# LD_driver.net
KiCad netlist of a schematic drawn in Altium Designer
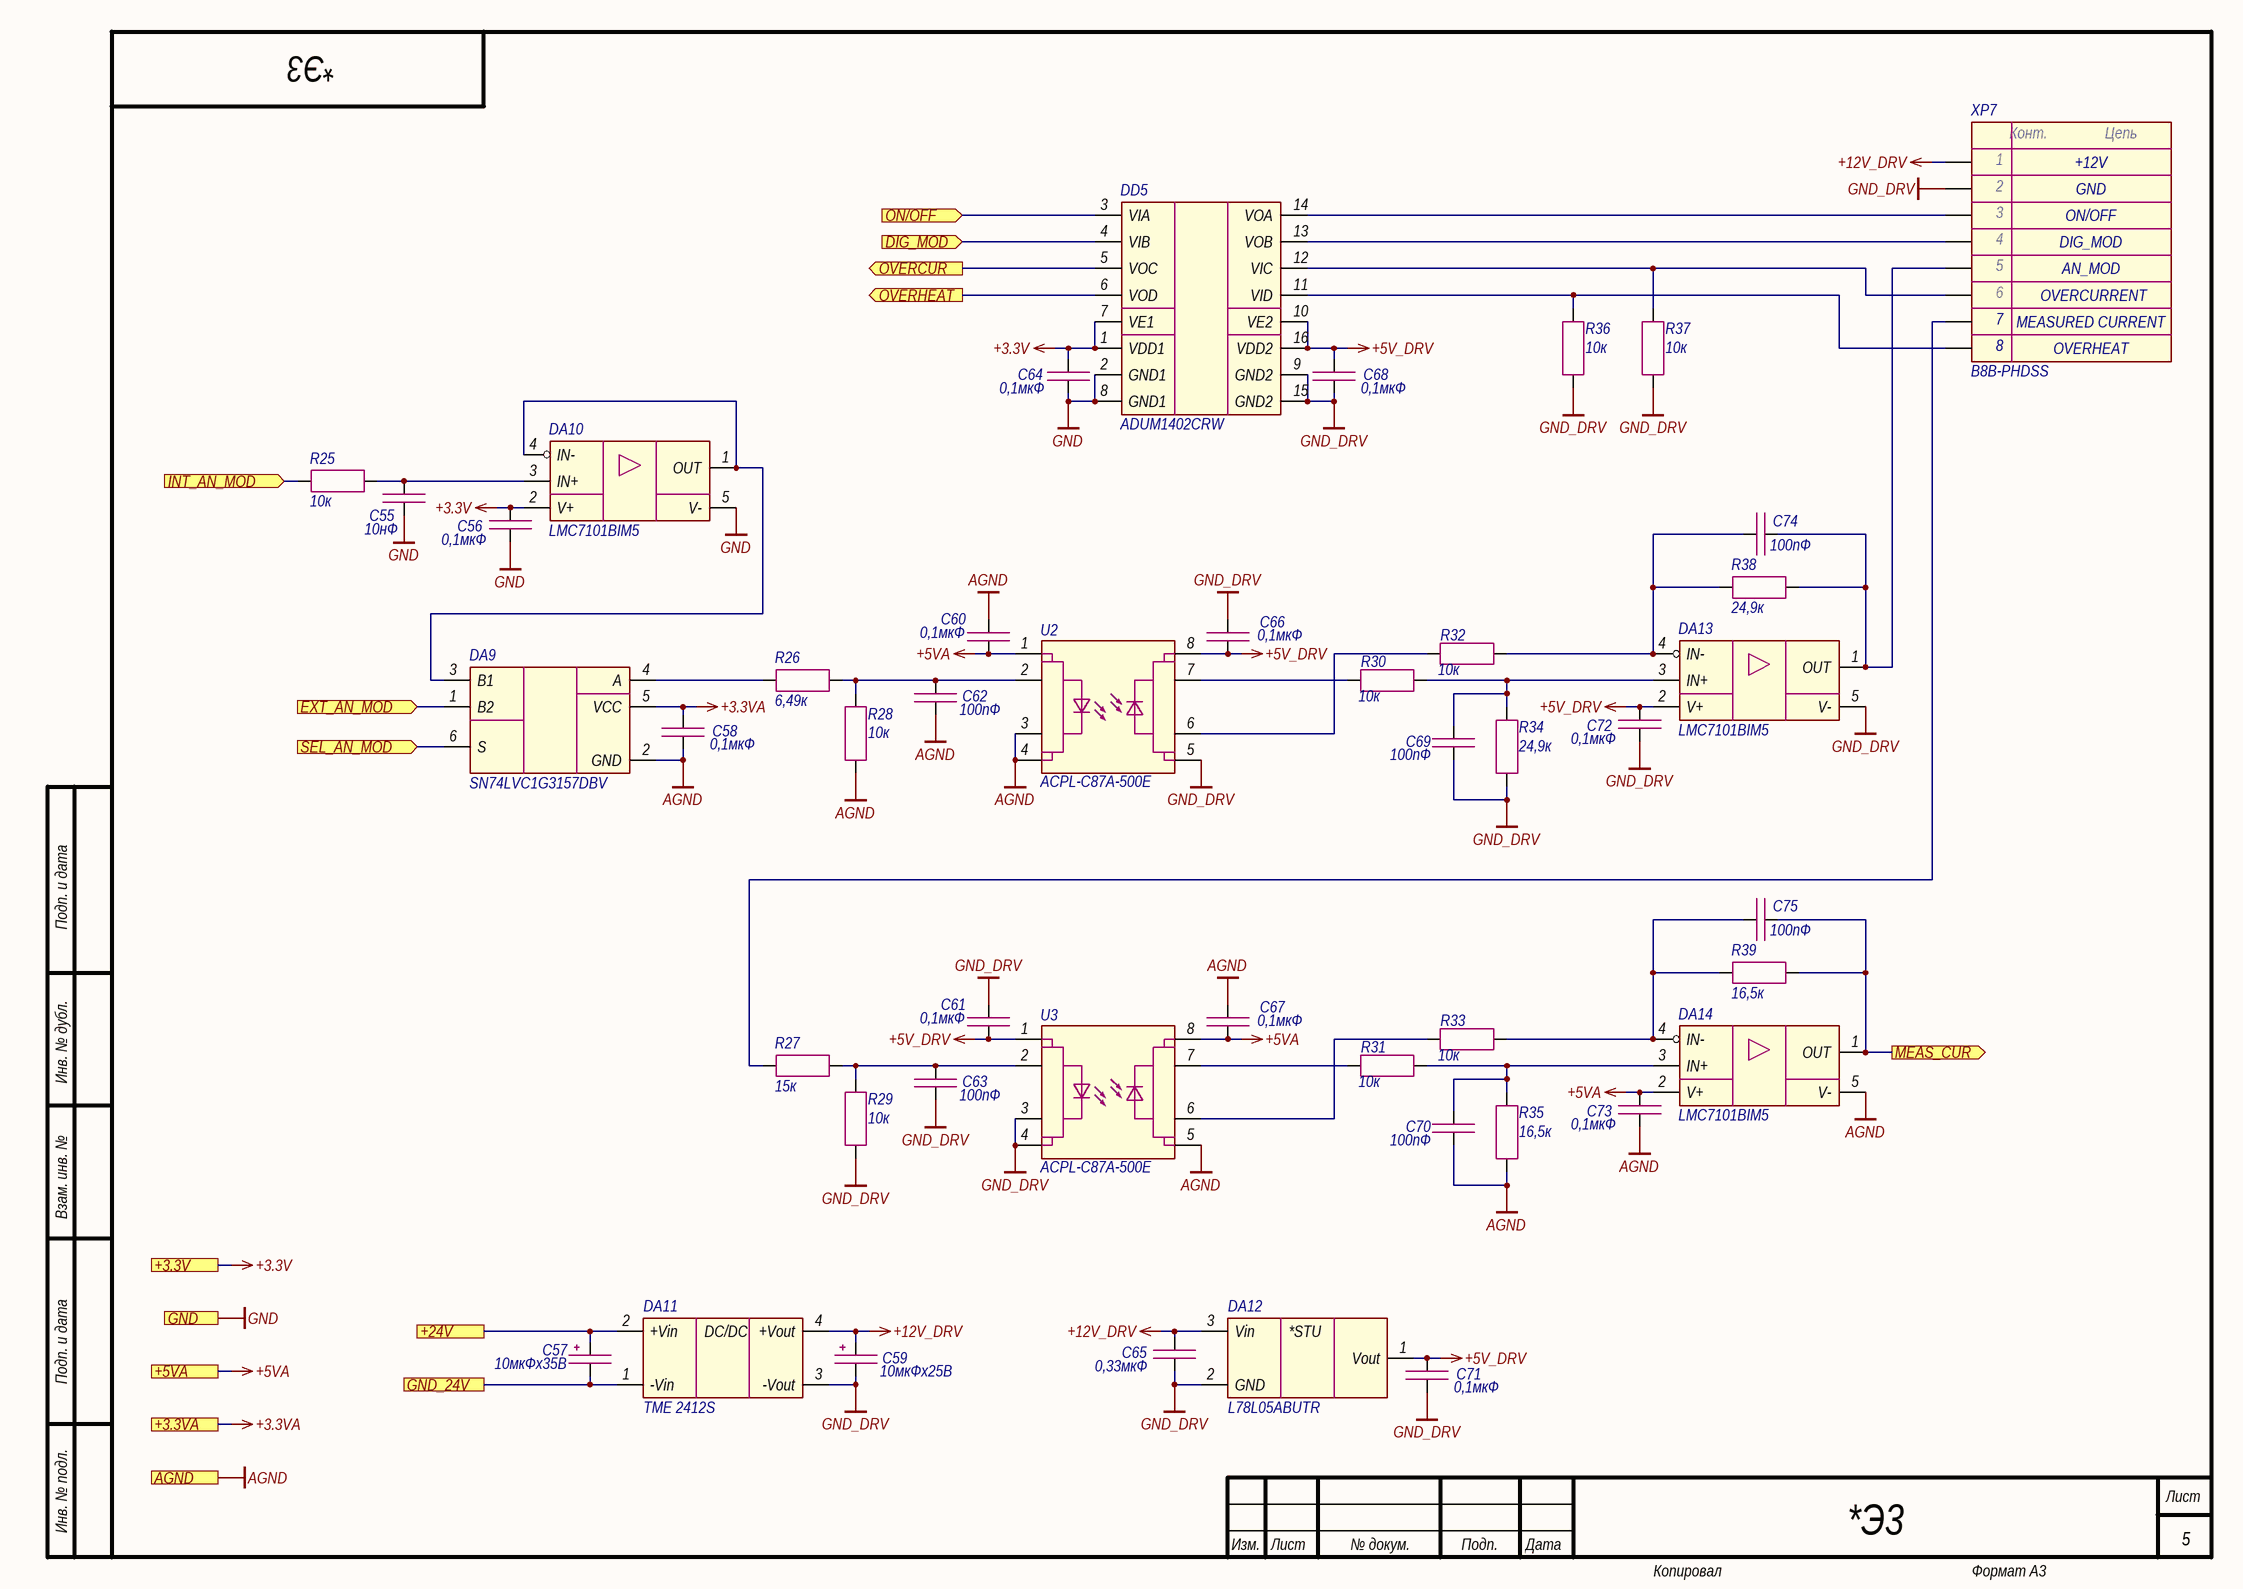
[diagram p0: LD_driver.SchDoc]

(export (version "E")
  (design (tool "Eeschema 10.0.6"))
  (components
    (comp (ref "C55")
      (value "10нФ")
      (footprint "Pcb_library:CAP_0603")
      (fields (field (name "MANUFACTURER") "Murata"))
      (libsource (lib "Schem_library") (part "Capacitor"))
    )
    (comp (ref "C56")
      (value "0,1мкФ")
      (footprint "Pcb_library:CAP_0603")
      (fields (field (name "MANUFACTURER") "Murata"))
      (libsource (lib "Schem_library") (part "Capacitor"))
    )
    (comp (ref "C57")
      (value "10мкФх35B")
      (footprint "Pcb_library:CAP_C")
      (libsource (lib "Schem_library") (part "Capacitor_Polar"))
    )
    (comp (ref "C58")
      (value "0,1мкФ")
      (footprint "Pcb_library:CAP_0603")
      (fields (field (name "MANUFACTURER") "Murata"))
      (libsource (lib "Schem_library") (part "Capacitor"))
    )
    (comp (ref "C59")
      (value "10мкФх25B")
      (footprint "Pcb_library:CAP_C")
      (libsource (lib "Schem_library") (part "Capacitor_Polar"))
    )
    (comp (ref "C60")
      (value "0,1мкФ")
      (footprint "Pcb_library:CAP_0603")
      (fields (field (name "MANUFACTURER") "Murata"))
      (libsource (lib "Schem_library") (part "Capacitor"))
    )
    (comp (ref "C61")
      (value "0,1мкФ")
      (footprint "Pcb_library:CAP_0603")
      (fields (field (name "MANUFACTURER") "Murata"))
      (libsource (lib "Schem_library") (part "Capacitor"))
    )
    (comp (ref "C62")
      (value "100пФ")
      (footprint "Pcb_library:CAP_0603")
      (fields (field (name "MANUFACTURER") "Murata"))
      (libsource (lib "Schem_library") (part "Capacitor"))
    )
    (comp (ref "C63")
      (value "100пФ")
      (footprint "Pcb_library:CAP_0603")
      (fields (field (name "MANUFACTURER") "Murata"))
      (libsource (lib "Schem_library") (part "Capacitor"))
    )
    (comp (ref "C64")
      (value "0,1мкФ")
      (footprint "Pcb_library:CAP_0603")
      (fields (field (name "MANUFACTURER") "Murata"))
      (libsource (lib "Schem_library") (part "Capacitor"))
    )
    (comp (ref "C65")
      (value "0,33мкФ")
      (footprint "Pcb_library:CAP_0805")
      (fields (field (name "MANUFACTURER") "Murata"))
      (libsource (lib "Schem_library") (part "Capacitor"))
    )
    (comp (ref "C66")
      (value "0,1мкФ")
      (footprint "Pcb_library:CAP_0603")
      (fields (field (name "MANUFACTURER") "Murata"))
      (libsource (lib "Schem_library") (part "Capacitor"))
    )
    (comp (ref "C67")
      (value "0,1мкФ")
      (footprint "Pcb_library:CAP_0603")
      (fields (field (name "MANUFACTURER") "Murata"))
      (libsource (lib "Schem_library") (part "Capacitor"))
    )
    (comp (ref "C68")
      (value "0,1мкФ")
      (footprint "Pcb_library:CAP_0603")
      (fields (field (name "MANUFACTURER") "Murata"))
      (libsource (lib "Schem_library") (part "Capacitor"))
    )
    (comp (ref "C69")
      (value "100пФ")
      (footprint "Pcb_library:CAP_0603")
      (fields (field (name "MANUFACTURER") "Murata"))
      (libsource (lib "Schem_library") (part "Capacitor"))
    )
    (comp (ref "C70")
      (value "100пФ")
      (footprint "Pcb_library:CAP_0603")
      (fields (field (name "MANUFACTURER") "Murata"))
      (libsource (lib "Schem_library") (part "Capacitor"))
    )
    (comp (ref "C71")
      (value "0,1мкФ")
      (footprint "Pcb_library:CAP_0603")
      (fields (field (name "MANUFACTURER") "Murata"))
      (libsource (lib "Schem_library") (part "Capacitor"))
    )
    (comp (ref "C72")
      (value "0,1мкФ")
      (footprint "Pcb_library:CAP_0603")
      (fields (field (name "MANUFACTURER") "Murata"))
      (libsource (lib "Schem_library") (part "Capacitor"))
    )
    (comp (ref "C73")
      (value "0,1мкФ")
      (footprint "Pcb_library:CAP_0603")
      (fields (field (name "MANUFACTURER") "Murata"))
      (libsource (lib "Schem_library") (part "Capacitor"))
    )
    (comp (ref "C74")
      (value "100пФ")
      (footprint "Pcb_library:CAP_0603")
      (fields (field (name "MANUFACTURER") "Murata"))
      (libsource (lib "Schem_library") (part "Capacitor"))
    )
    (comp (ref "C75")
      (value "100пФ")
      (footprint "Pcb_library:CAP_0603")
      (fields (field (name "MANUFACTURER") "Murata"))
      (libsource (lib "Schem_library") (part "Capacitor"))
    )
    (comp (ref "DA9")
      (value "SN74LVC1G3157DBV")
      (footprint "Pcb_library:SOT-23-6")
      (fields (field (name "MANUFACTURER") "Texas Instruments"))
      (libsource (lib "Schem_library") (part "SN74LVC1G3157"))
    )
    (comp (ref "DA10")
      (value "LMC7101BIM5")
      (footprint "Pcb_library:SOT-23-5")
      (fields (field (name "MANUFACTURER") "Texas Instruments"))
      (libsource (lib "Schem_library") (part "LMC7101"))
    )
    (comp (ref "DA11")
      (value "TME 2412S")
      (footprint "Pcb_library:TME (SIP-4)")
      (fields (field (name "MANUFACTURER") "Traco Power"))
      (libsource (lib "Schem_library") (part "TME"))
    )
    (comp (ref "DA12")
      (value "L78L05ABUTR")
      (footprint "Pcb_library:SOT-89")
      (fields (field (name "MANUFACTURER") "STMicroelectronics"))
      (libsource (lib "Schem_library") (part "LD2981ABU50TR"))
    )
    (comp (ref "DA13")
      (value "LMC7101BIM5")
      (footprint "Pcb_library:SOT-23-5")
      (fields (field (name "MANUFACTURER") "Texas Instruments"))
      (libsource (lib "Schem_library") (part "LMC7101"))
    )
    (comp (ref "DA14")
      (value "LMC7101BIM5")
      (footprint "Pcb_library:SOT-23-5")
      (fields (field (name "MANUFACTURER") "Texas Instruments"))
      (libsource (lib "Schem_library") (part "LMC7101"))
    )
    (comp (ref "DD5")
      (value "ADUM1402CRW")
      (footprint "Pcb_library:SOIC-16W")
      (fields (field (name "MANUFACTURER") "Analog Devices"))
      (libsource (lib "Schem_library") (part "ADUM1402"))
    )
    (comp (ref "R25")
      (value "10к")
      (footprint "Pcb_library:RES_0603")
      (fields (field (name "MANUFACTURER") "Yageo"))
      (libsource (lib "Schem_library") (part "Resistor"))
    )
    (comp (ref "R26")
      (value "6,49к")
      (footprint "Pcb_library:RES_0603")
      (fields (field (name "MANUFACTURER") "Yageo"))
      (libsource (lib "Schem_library") (part "Resistor"))
    )
    (comp (ref "R27")
      (value "15к")
      (footprint "Pcb_library:RES_0603")
      (fields (field (name "MANUFACTURER") "Yageo"))
      (libsource (lib "Schem_library") (part "Resistor"))
    )
    (comp (ref "R28")
      (value "10к")
      (footprint "Pcb_library:RES_0603")
      (fields (field (name "MANUFACTURER") "Yageo"))
      (libsource (lib "Schem_library") (part "Resistor"))
    )
    (comp (ref "R29")
      (value "10к")
      (footprint "Pcb_library:RES_0603")
      (fields (field (name "MANUFACTURER") "Yageo"))
      (libsource (lib "Schem_library") (part "Resistor"))
    )
    (comp (ref "R30")
      (value "10к")
      (footprint "Pcb_library:RES_0603")
      (fields (field (name "MANUFACTURER") "Yageo"))
      (libsource (lib "Schem_library") (part "Resistor"))
    )
    (comp (ref "R31")
      (value "10к")
      (footprint "Pcb_library:RES_0603")
      (fields (field (name "MANUFACTURER") "Yageo"))
      (libsource (lib "Schem_library") (part "Resistor"))
    )
    (comp (ref "R32")
      (value "10к")
      (footprint "Pcb_library:RES_0603")
      (fields (field (name "MANUFACTURER") "Yageo"))
      (libsource (lib "Schem_library") (part "Resistor"))
    )
    (comp (ref "R33")
      (value "10к")
      (footprint "Pcb_library:RES_0603")
      (fields (field (name "MANUFACTURER") "Yageo"))
      (libsource (lib "Schem_library") (part "Resistor"))
    )
    (comp (ref "R34")
      (value "24,9к")
      (footprint "Pcb_library:RES_0603")
      (fields (field (name "MANUFACTURER") "Yageo"))
      (libsource (lib "Schem_library") (part "Resistor"))
    )
    (comp (ref "R35")
      (value "16,5к")
      (footprint "Pcb_library:RES_0603")
      (fields (field (name "MANUFACTURER") "Yageo"))
      (libsource (lib "Schem_library") (part "Resistor"))
    )
    (comp (ref "R36")
      (value "10к")
      (footprint "Pcb_library:RES_0603")
      (fields (field (name "MANUFACTURER") "Yageo"))
      (libsource (lib "Schem_library") (part "Resistor"))
    )
    (comp (ref "R37")
      (value "10к")
      (footprint "Pcb_library:RES_0603")
      (fields (field (name "MANUFACTURER") "Yageo"))
      (libsource (lib "Schem_library") (part "Resistor"))
    )
    (comp (ref "R38")
      (value "24,9к")
      (footprint "Pcb_library:RES_0603")
      (fields (field (name "MANUFACTURER") "Yageo"))
      (libsource (lib "Schem_library") (part "Resistor"))
    )
    (comp (ref "R39")
      (value "16,5к")
      (footprint "Pcb_library:RES_0603")
      (fields (field (name "MANUFACTURER") "Yageo"))
      (libsource (lib "Schem_library") (part "Resistor"))
    )
    (comp (ref "U2")
      (value "ACPL-C87A-500E")
      (footprint "Pcb_library:SSO-8")
      (fields (field (name "MANUFACTURER") "Broadcom"))
      (libsource (lib "Schem_library") (part "ACPL-C87"))
    )
    (comp (ref "U3")
      (value "ACPL-C87A-500E")
      (footprint "Pcb_library:SSO-8")
      (fields (field (name "MANUFACTURER") "Broadcom"))
      (libsource (lib "Schem_library") (part "ACPL-C87"))
    )
    (comp (ref "XP7")
      (value "B8B-PHDSS")
      (footprint "Pcb_library:B8B-PHDSS")
      (fields (field (name "MANUFACTURER") "JST"))
      (libsource (lib "Schem_library") (part "Connector-8"))
    )
  )
  (nets
    (net (code "1") (name "+3.3V") (class "Default")
      (node (ref "C56") (pin "1") (pinfunction "1_1") (pintype "passive"))
      (node (ref "C64") (pin "1") (pinfunction "1_1") (pintype "passive"))
      (node (ref "DA10") (pin "2") (pinfunction "V+_2") (pintype "passive"))
      (node (ref "DD5") (pin "1") (pinfunction "VDD1_1") (pintype "passive"))
      (node (ref "DD5") (pin "7") (pinfunction "VE1_7") (pintype "passive"))
    )
    (net (code "2") (name "+3.3VA") (class "Default")
      (node (ref "C58") (pin "1") (pinfunction "1_1") (pintype "passive"))
      (node (ref "DA9") (pin "5") (pinfunction "VCC_5") (pintype "passive"))
    )
    (net (code "3") (name "+5VA") (class "Default")
      (node (ref "C60") (pin "1") (pinfunction "1_1") (pintype "passive"))
      (node (ref "C67") (pin "1") (pinfunction "1_1") (pintype "passive"))
      (node (ref "C73") (pin "1") (pinfunction "1_1") (pintype "passive"))
      (node (ref "DA14") (pin "2") (pinfunction "V+_2") (pintype "passive"))
      (node (ref "U2") (pin "1") (pinfunction "VDD1_1") (pintype "passive"))
      (node (ref "U3") (pin "8") (pinfunction "VDD2_8") (pintype "passive"))
    )
    (net (code "4") (name "+5V_DRV") (class "Default")
      (node (ref "C61") (pin "1") (pinfunction "1_1") (pintype "passive"))
      (node (ref "C66") (pin "1") (pinfunction "1_1") (pintype "passive"))
      (node (ref "C68") (pin "1") (pinfunction "1_1") (pintype "passive"))
      (node (ref "C71") (pin "1") (pinfunction "1_1") (pintype "passive"))
      (node (ref "C72") (pin "1") (pinfunction "1_1") (pintype "passive"))
      (node (ref "DA12") (pin "1") (pinfunction "Vout_1") (pintype "passive"))
      (node (ref "DA13") (pin "2") (pinfunction "V+_2") (pintype "passive"))
      (node (ref "DD5") (pin "10") (pinfunction "VE2_10") (pintype "passive"))
      (node (ref "DD5") (pin "16") (pinfunction "VDD2_16") (pintype "passive"))
      (node (ref "U2") (pin "8") (pinfunction "VDD2_8") (pintype "passive"))
      (node (ref "U3") (pin "1") (pinfunction "VDD1_1") (pintype "passive"))
    )
    (net (code "5") (name "+12V_DRV") (class "Default")
      (node (ref "C59") (pin "1") (pinfunction "1_1") (pintype "passive"))
      (node (ref "C65") (pin "2") (pinfunction "2_2") (pintype "passive"))
      (node (ref "DA11") (pin "4") (pinfunction "+Vout_4") (pintype "passive"))
      (node (ref "DA12") (pin "3") (pinfunction "Vin_3") (pintype "passive"))
      (node (ref "XP7") (pin "1") (pintype "passive"))
    )
    (net (code "6") (name "/+24V") (class "Default")
      (node (ref "C57") (pin "1") (pinfunction "1_1") (pintype "passive"))
      (node (ref "DA11") (pin "2") (pinfunction "+Vin_2") (pintype "passive"))
    )
    (net (code "7") (name "/DIG_MOD") (class "Default")
      (node (ref "DD5") (pin "4") (pinfunction "VIB_4") (pintype "passive"))
    )
    (net (code "8") (name "/EXT_AN_MOD") (class "Default")
      (node (ref "DA9") (pin "1") (pinfunction "B2_1") (pintype "passive"))
    )
    (net (code "9") (name "/GND_24V") (class "Default")
      (node (ref "C57") (pin "2") (pinfunction "2_2") (pintype "passive"))
      (node (ref "DA11") (pin "1") (pinfunction "-Vin_1") (pintype "passive"))
    )
    (net (code "10") (name "/INT_AN_MOD") (class "Default")
      (node (ref "R25") (pin "1") (pinfunction "1_1") (pintype "passive"))
    )
    (net (code "11") (name "/MEAS_CUR") (class "Default")
      (node (ref "C75") (pin "2") (pinfunction "2_2") (pintype "passive"))
      (node (ref "DA14") (pin "1") (pinfunction "OUT_1") (pintype "passive"))
      (node (ref "R39") (pin "1") (pinfunction "1_1") (pintype "passive"))
    )
    (net (code "12") (name "/ON{slash}OFF") (class "Default")
      (node (ref "DD5") (pin "3") (pinfunction "VIA_3") (pintype "passive"))
    )
    (net (code "13") (name "/OVERCUR") (class "Default")
      (node (ref "DD5") (pin "5") (pinfunction "VOC_5") (pintype "passive"))
    )
    (net (code "14") (name "/OVERHEAT") (class "Default")
      (node (ref "DD5") (pin "6") (pinfunction "VOD_6") (pintype "passive"))
    )
    (net (code "15") (name "/SEL_AN_MOD") (class "Default")
      (node (ref "DA9") (pin "6") (pinfunction "S_6") (pintype "passive"))
    )
    (net (code "16") (name "AGND") (class "Default")
      (node (ref "C58") (pin "2") (pinfunction "2_2") (pintype "passive"))
      (node (ref "C60") (pin "2") (pinfunction "2_2") (pintype "passive"))
      (node (ref "C62") (pin "1") (pinfunction "1_1") (pintype "passive"))
      (node (ref "C67") (pin "2") (pinfunction "2_2") (pintype "passive"))
      (node (ref "C70") (pin "2") (pinfunction "2_2") (pintype "passive"))
      (node (ref "C73") (pin "2") (pinfunction "2_2") (pintype "passive"))
      (node (ref "DA14") (pin "5") (pinfunction "V-_5") (pintype "passive"))
      (node (ref "DA9") (pin "2") (pinfunction "GND_2") (pintype "passive"))
      (node (ref "R28") (pin "2") (pinfunction "2_2") (pintype "passive"))
      (node (ref "R35") (pin "2") (pinfunction "2_2") (pintype "passive"))
      (node (ref "U2") (pin "3") (pinfunction "SHDN_3") (pintype "passive"))
      (node (ref "U2") (pin "4") (pinfunction "GND1_4") (pintype "passive"))
      (node (ref "U3") (pin "5") (pinfunction "GND2_5") (pintype "passive"))
    )
    (net (code "17") (name "GND") (class "Default")
      (node (ref "C55") (pin "2") (pinfunction "2_2") (pintype "passive"))
      (node (ref "C56") (pin "2") (pinfunction "2_2") (pintype "passive"))
      (node (ref "C64") (pin "2") (pinfunction "2_2") (pintype "passive"))
      (node (ref "DA10") (pin "5") (pinfunction "V-_5") (pintype "passive"))
      (node (ref "DD5") (pin "2") (pinfunction "GND1_2") (pintype "passive"))
      (node (ref "DD5") (pin "8") (pinfunction "GND1_8") (pintype "passive"))
    )
    (net (code "18") (name "GND_DRV") (class "Default")
      (node (ref "C59") (pin "2") (pinfunction "2_2") (pintype "passive"))
      (node (ref "C61") (pin "2") (pinfunction "2_2") (pintype "passive"))
      (node (ref "C63") (pin "1") (pinfunction "1_1") (pintype "passive"))
      (node (ref "C65") (pin "1") (pinfunction "1_1") (pintype "passive"))
      (node (ref "C66") (pin "2") (pinfunction "2_2") (pintype "passive"))
      (node (ref "C68") (pin "2") (pinfunction "2_2") (pintype "passive"))
      (node (ref "C69") (pin "2") (pinfunction "2_2") (pintype "passive"))
      (node (ref "C71") (pin "2") (pinfunction "2_2") (pintype "passive"))
      (node (ref "C72") (pin "2") (pinfunction "2_2") (pintype "passive"))
      (node (ref "DA11") (pin "3") (pinfunction "-Vout_3") (pintype "passive"))
      (node (ref "DA12") (pin "2") (pinfunction "GND_2") (pintype "passive"))
      (node (ref "DA13") (pin "5") (pinfunction "V-_5") (pintype "passive"))
      (node (ref "DD5") (pin "15") (pinfunction "GND2_15") (pintype "passive"))
      (node (ref "DD5") (pin "9") (pinfunction "GND2_9") (pintype "passive"))
      (node (ref "R29") (pin "2") (pinfunction "2_2") (pintype "passive"))
      (node (ref "R34") (pin "1") (pinfunction "1_1") (pintype "passive"))
      (node (ref "R36") (pin "2") (pinfunction "2_2") (pintype "passive"))
      (node (ref "R37") (pin "2") (pinfunction "2_2") (pintype "passive"))
      (node (ref "U2") (pin "5") (pinfunction "GND2_5") (pintype "passive"))
      (node (ref "U3") (pin "3") (pinfunction "SHDN_3") (pintype "passive"))
      (node (ref "U3") (pin "4") (pinfunction "GND1_4") (pintype "passive"))
      (node (ref "XP7") (pin "2") (pintype "passive"))
    )
    (net (code "19") (name "Net-(DA9-A)") (class "Default")
      (node (ref "DA9") (pin "4") (pinfunction "A_4") (pintype "passive"))
      (node (ref "R26") (pin "2") (pinfunction "2_2") (pintype "passive"))
    )
    (net (code "20") (name "Net-(DA10-IN+)") (class "Default")
      (node (ref "C55") (pin "1") (pinfunction "1_1") (pintype "passive"))
      (node (ref "DA10") (pin "3") (pinfunction "IN+_3") (pintype "passive"))
      (node (ref "R25") (pin "2") (pinfunction "2_2") (pintype "passive"))
    )
    (net (code "21") (name "Net-(DA10-IN-)") (class "Default")
      (node (ref "DA10") (pin "1") (pinfunction "OUT_1") (pintype "passive"))
      (node (ref "DA10") (pin "4") (pinfunction "IN-_4") (pintype "passive"))
      (node (ref "DA9") (pin "3") (pinfunction "B1_3") (pintype "passive"))
    )
    (net (code "22") (name "Net-(DA13-IN+)") (class "Default")
      (node (ref "C69") (pin "1") (pinfunction "1_1") (pintype "passive"))
      (node (ref "DA13") (pin "3") (pinfunction "IN+_3") (pintype "passive"))
      (node (ref "R30") (pin "2") (pinfunction "2_2") (pintype "passive"))
      (node (ref "R34") (pin "2") (pinfunction "2_2") (pintype "passive"))
    )
    (net (code "23") (name "Net-(DA13-IN-)") (class "Default")
      (node (ref "C74") (pin "1") (pinfunction "1_1") (pintype "passive"))
      (node (ref "DA13") (pin "4") (pinfunction "IN-_4") (pintype "passive"))
      (node (ref "R32") (pin "2") (pinfunction "2_2") (pintype "passive"))
      (node (ref "R38") (pin "1") (pinfunction "1_1") (pintype "passive"))
    )
    (net (code "24") (name "Net-(DA13-OUT)") (class "Default")
      (node (ref "C74") (pin "2") (pinfunction "2_2") (pintype "passive"))
      (node (ref "DA13") (pin "1") (pinfunction "OUT_1") (pintype "passive"))
      (node (ref "R38") (pin "2") (pinfunction "2_2") (pintype "passive"))
      (node (ref "XP7") (pin "5") (pintype "passive"))
    )
    (net (code "25") (name "Net-(DA14-IN+)") (class "Default")
      (node (ref "C70") (pin "1") (pinfunction "1_1") (pintype "passive"))
      (node (ref "DA14") (pin "3") (pinfunction "IN+_3") (pintype "passive"))
      (node (ref "R31") (pin "2") (pinfunction "2_2") (pintype "passive"))
      (node (ref "R35") (pin "1") (pinfunction "1_1") (pintype "passive"))
    )
    (net (code "26") (name "Net-(DA14-IN-)") (class "Default")
      (node (ref "C75") (pin "1") (pinfunction "1_1") (pintype "passive"))
      (node (ref "DA14") (pin "4") (pinfunction "IN-_4") (pintype "passive"))
      (node (ref "R33") (pin "2") (pinfunction "2_2") (pintype "passive"))
      (node (ref "R39") (pin "2") (pinfunction "2_2") (pintype "passive"))
    )
    (net (code "27") (name "Net-(DD5-VIC)") (class "Default")
      (node (ref "DD5") (pin "12") (pinfunction "VIC_12") (pintype "passive"))
      (node (ref "R37") (pin "1") (pinfunction "1_1") (pintype "passive"))
      (node (ref "XP7") (pin "6") (pintype "passive"))
    )
    (net (code "28") (name "Net-(DD5-VID)") (class "Default")
      (node (ref "DD5") (pin "11") (pinfunction "VID_11") (pintype "passive"))
      (node (ref "R36") (pin "1") (pinfunction "1_1") (pintype "passive"))
      (node (ref "XP7") (pin "8") (pintype "passive"))
    )
    (net (code "29") (name "Net-(DD5-VOA)") (class "Default")
      (node (ref "DD5") (pin "14") (pinfunction "VOA_14") (pintype "passive"))
      (node (ref "XP7") (pin "3") (pintype "passive"))
    )
    (net (code "30") (name "Net-(DD5-VOB)") (class "Default")
      (node (ref "DD5") (pin "13") (pinfunction "VOB_13") (pintype "passive"))
      (node (ref "XP7") (pin "4") (pintype "passive"))
    )
    (net (code "31") (name "Net-(R27-Pad2)") (class "Default")
      (node (ref "R27") (pin "2") (pinfunction "2_2") (pintype "passive"))
      (node (ref "XP7") (pin "7") (pintype "passive"))
    )
    (net (code "32") (name "Net-(U2-VIN)") (class "Default")
      (node (ref "C62") (pin "2") (pinfunction "2_2") (pintype "passive"))
      (node (ref "R26") (pin "1") (pinfunction "1_1") (pintype "passive"))
      (node (ref "R28") (pin "1") (pinfunction "1_1") (pintype "passive"))
      (node (ref "U2") (pin "2") (pinfunction "VIN_2") (pintype "passive"))
    )
    (net (code "33") (name "Net-(U2-VOUT+)") (class "Default")
      (node (ref "R30") (pin "1") (pinfunction "1_1") (pintype "passive"))
      (node (ref "U2") (pin "7") (pinfunction "VOUT+_7") (pintype "passive"))
    )
    (net (code "34") (name "Net-(U2-VOUT-)") (class "Default")
      (node (ref "R32") (pin "1") (pinfunction "1_1") (pintype "passive"))
      (node (ref "U2") (pin "6") (pinfunction "VOUT-_6") (pintype "passive"))
    )
    (net (code "35") (name "Net-(U3-VIN)") (class "Default")
      (node (ref "C63") (pin "2") (pinfunction "2_2") (pintype "passive"))
      (node (ref "R27") (pin "1") (pinfunction "1_1") (pintype "passive"))
      (node (ref "R29") (pin "1") (pinfunction "1_1") (pintype "passive"))
      (node (ref "U3") (pin "2") (pinfunction "VIN_2") (pintype "passive"))
    )
    (net (code "36") (name "Net-(U3-VOUT+)") (class "Default")
      (node (ref "R31") (pin "1") (pinfunction "1_1") (pintype "passive"))
      (node (ref "U3") (pin "7") (pinfunction "VOUT+_7") (pintype "passive"))
    )
    (net (code "37") (name "Net-(U3-VOUT-)") (class "Default")
      (node (ref "R33") (pin "1") (pinfunction "1_1") (pintype "passive"))
      (node (ref "U3") (pin "6") (pinfunction "VOUT-_6") (pintype "passive"))
    )
  )
)
